# HF_TUNER.net
KiCad netlist of a schematic drawn in Altium Designer
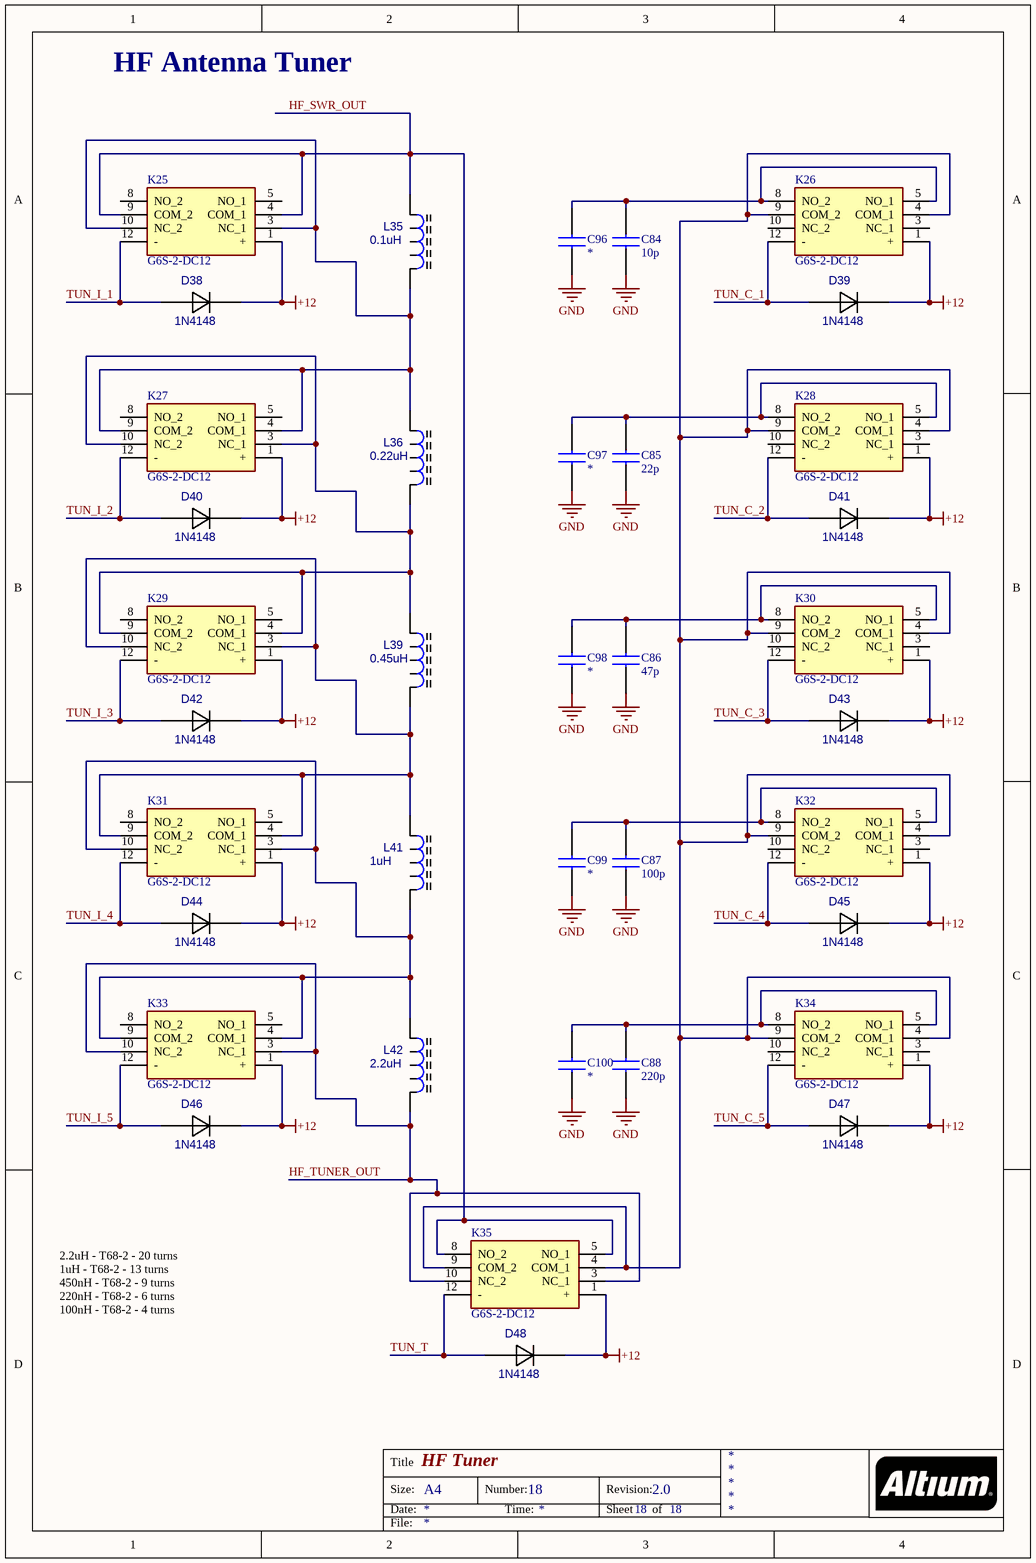
[diagram p0: HF_TUNER.SchDoc]

(export (version "E")
  (design (tool "Eeschema 10.0.6"))
  (components
    (comp (ref "C84")
      (value "10p")
      (footprint "SamacSys:B32620A0682J000")
      (description "Capacitor")
      (fields
        (field (name "MANUFACTURER_PART_NUMBER") "B32620A0682J000")
        (field (name "MOUSER PART NUMBER") "871-B32620A682J")
      )
      (libsource (lib "*") (part "B32620A0682J000"))
    )
    (comp (ref "C85")
      (value "22p")
      (footprint "SamacSys:B32620A0682J000")
      (description "Capacitor")
      (fields
        (field (name "MANUFACTURER_PART_NUMBER") "B32620A0682J000")
        (field (name "MOUSER PART NUMBER") "871-B32620A682J")
      )
      (libsource (lib "*") (part "B32620A0682J000"))
    )
    (comp (ref "C86")
      (value "47p")
      (footprint "SamacSys:B32620A0682J000")
      (description "Capacitor")
      (fields
        (field (name "MANUFACTURER_PART_NUMBER") "B32620A0682J000")
        (field (name "MOUSER PART NUMBER") "871-B32620A682J")
      )
      (libsource (lib "*") (part "B32620A0682J000"))
    )
    (comp (ref "C87")
      (value "100p")
      (footprint "SamacSys:B32620A0682J000")
      (description "Capacitor")
      (fields
        (field (name "MANUFACTURER_PART_NUMBER") "B32620A0682J000")
        (field (name "MOUSER PART NUMBER") "871-B32620A682J")
      )
      (libsource (lib "*") (part "B32620A0682J000"))
    )
    (comp (ref "C88")
      (value "220p")
      (footprint "SamacSys:B32620A0682J000")
      (description "Capacitor")
      (fields
        (field (name "MANUFACTURER_PART_NUMBER") "B32620A0682J000")
        (field (name "MOUSER PART NUMBER") "871-B32620A682J")
      )
      (libsource (lib "*") (part "B32620A0682J000"))
    )
    (comp (ref "C96")
      (value "*")
      (footprint "CAP_1206")
      (description "Capacitor NP0 HiVolt")
      (fields
        (field (name "MANUFACTURER_PART_NUMBER") "B32620A0682J000")
        (field (name "MOUSER PART NUMBER") "871-B32620A682J")
      )
      (libsource (lib "*") (part "B32620A0682J000"))
    )
    (comp (ref "C97")
      (value "*")
      (footprint "CAP_1206")
      (description "Capacitor NP0 HiVolt")
      (fields
        (field (name "MANUFACTURER_PART_NUMBER") "B32620A0682J000")
        (field (name "MOUSER PART NUMBER") "871-B32620A682J")
      )
      (libsource (lib "*") (part "B32620A0682J000"))
    )
    (comp (ref "C98")
      (value "*")
      (footprint "CAP_1206")
      (description "Capacitor NP0 HiVolt")
      (fields
        (field (name "MANUFACTURER_PART_NUMBER") "B32620A0682J000")
        (field (name "MOUSER PART NUMBER") "871-B32620A682J")
      )
      (libsource (lib "*") (part "B32620A0682J000"))
    )
    (comp (ref "C99")
      (value "*")
      (footprint "CAP_1206")
      (description "Capacitor NP0 HiVolt")
      (fields
        (field (name "MANUFACTURER_PART_NUMBER") "B32620A0682J000")
        (field (name "MOUSER PART NUMBER") "871-B32620A682J")
      )
      (libsource (lib "*") (part "B32620A0682J000"))
    )
    (comp (ref "C100")
      (value "*")
      (footprint "CAP_1206")
      (description "Capacitor NP0 HiVolt")
      (fields
        (field (name "MANUFACTURER_PART_NUMBER") "B32620A0682J000")
        (field (name "MOUSER PART NUMBER") "871-B32620A682J")
      )
      (libsource (lib "*") (part "B32620A0682J000"))
    )
    (comp (ref "D38") (value "1N4148") (footprint "SS14") (libsource (lib "RF-UNIT-BIG") (part "1N4148")))
    (comp (ref "D39") (value "1N4148") (footprint "SS14") (libsource (lib "RF-UNIT-BIG") (part "1N4148")))
    (comp (ref "D40") (value "1N4148") (footprint "SS14") (libsource (lib "RF-UNIT-BIG") (part "1N4148")))
    (comp (ref "D41") (value "1N4148") (footprint "SS14") (libsource (lib "RF-UNIT-BIG") (part "1N4148")))
    (comp (ref "D42") (value "1N4148") (footprint "SS14") (libsource (lib "RF-UNIT-BIG") (part "1N4148")))
    (comp (ref "D43") (value "1N4148") (footprint "SS14") (libsource (lib "RF-UNIT-BIG") (part "1N4148")))
    (comp (ref "D44") (value "1N4148") (footprint "SS14") (libsource (lib "RF-UNIT-BIG") (part "1N4148")))
    (comp (ref "D45") (value "1N4148") (footprint "SS14") (libsource (lib "RF-UNIT-BIG") (part "1N4148")))
    (comp (ref "D46") (value "1N4148") (footprint "SS14") (libsource (lib "RF-UNIT-BIG") (part "1N4148")))
    (comp (ref "D47") (value "1N4148") (footprint "SS14") (libsource (lib "RF-UNIT-BIG") (part "1N4148")))
    (comp (ref "D48") (value "1N4148") (footprint "SS14") (libsource (lib "RF-UNIT-BIG") (part "1N4148")))
    (comp (ref "K25")
      (value "G6S-2-DC12")
      (footprint "SamacSys:G6S2DC12")
      (description "Relay or Contactor")
      (fields (field (name "MOUSER PART NUMBER") "653-G6S-2-DC12A"))
      (libsource (lib "*") (part "G6S-2-DC12"))
    )
    (comp (ref "K26")
      (value "G6S-2-DC12")
      (footprint "SamacSys:G6S2DC12")
      (description "Relay or Contactor")
      (fields (field (name "MOUSER PART NUMBER") "653-G6S-2-DC12A"))
      (libsource (lib "*") (part "G6S-2-DC12"))
    )
    (comp (ref "K27")
      (value "G6S-2-DC12")
      (footprint "SamacSys:G6S2DC12")
      (description "Relay or Contactor")
      (fields (field (name "MOUSER PART NUMBER") "653-G6S-2-DC12A"))
      (libsource (lib "*") (part "G6S-2-DC12"))
    )
    (comp (ref "K28")
      (value "G6S-2-DC12")
      (footprint "SamacSys:G6S2DC12")
      (description "Relay or Contactor")
      (fields (field (name "MOUSER PART NUMBER") "653-G6S-2-DC12A"))
      (libsource (lib "*") (part "G6S-2-DC12"))
    )
    (comp (ref "K29")
      (value "G6S-2-DC12")
      (footprint "SamacSys:G6S2DC12")
      (description "Relay or Contactor")
      (fields (field (name "MOUSER PART NUMBER") "653-G6S-2-DC12A"))
      (libsource (lib "*") (part "G6S-2-DC12"))
    )
    (comp (ref "K30")
      (value "G6S-2-DC12")
      (footprint "SamacSys:G6S2DC12")
      (description "Relay or Contactor")
      (fields (field (name "MOUSER PART NUMBER") "653-G6S-2-DC12A"))
      (libsource (lib "*") (part "G6S-2-DC12"))
    )
    (comp (ref "K31")
      (value "G6S-2-DC12")
      (footprint "SamacSys:G6S2DC12")
      (description "Relay or Contactor")
      (fields (field (name "MOUSER PART NUMBER") "653-G6S-2-DC12A"))
      (libsource (lib "*") (part "G6S-2-DC12"))
    )
    (comp (ref "K32")
      (value "G6S-2-DC12")
      (footprint "SamacSys:G6S2DC12")
      (description "Relay or Contactor")
      (fields (field (name "MOUSER PART NUMBER") "653-G6S-2-DC12A"))
      (libsource (lib "*") (part "G6S-2-DC12"))
    )
    (comp (ref "K33")
      (value "G6S-2-DC12")
      (footprint "SamacSys:G6S2DC12")
      (description "Relay or Contactor")
      (fields (field (name "MOUSER PART NUMBER") "653-G6S-2-DC12A"))
      (libsource (lib "*") (part "G6S-2-DC12"))
    )
    (comp (ref "K34")
      (value "G6S-2-DC12")
      (footprint "SamacSys:G6S2DC12")
      (description "Relay or Contactor")
      (fields (field (name "MOUSER PART NUMBER") "653-G6S-2-DC12A"))
      (libsource (lib "*") (part "G6S-2-DC12"))
    )
    (comp (ref "K35")
      (value "G6S-2-DC12")
      (footprint "SamacSys:G6S2DC12")
      (description "Relay or Contactor")
      (fields (field (name "MOUSER PART NUMBER") "653-G6S-2-DC12A"))
      (libsource (lib "*") (part "G6S-2-DC12"))
    )
    (comp (ref "L35")
      (value "0.1uH")
      (footprint "IND_FERRITE_CORE_1")
      (description "Inductor")
      (libsource (lib "*") (part "IND_FERRITE_CORE"))
    )
    (comp (ref "L36")
      (value "0.22uH")
      (footprint "IND_FERRITE_CORE_1")
      (description "Inductor")
      (libsource (lib "*") (part "IND_FERRITE_CORE"))
    )
    (comp (ref "L39")
      (value "0.45uH")
      (footprint "IND_FERRITE_CORE_1")
      (description "Inductor")
      (libsource (lib "*") (part "IND_FERRITE_CORE"))
    )
    (comp (ref "L41")
      (value "1uH")
      (footprint "IND_FERRITE_CORE_1")
      (description "Inductor")
      (libsource (lib "*") (part "IND_FERRITE_CORE"))
    )
    (comp (ref "L42")
      (value "2.2uH")
      (footprint "IND_FERRITE_CORE_1")
      (description "Inductor")
      (libsource (lib "*") (part "IND_FERRITE_CORE"))
    )
  )
  (nets
    (net (code "1") (name "+12") (class "Default")
      (node (ref "D38") (pin "1") (pinfunction "K_1") (pintype "passive"))
      (node (ref "D39") (pin "1") (pinfunction "K_1") (pintype "passive"))
      (node (ref "D40") (pin "1") (pinfunction "K_1") (pintype "passive"))
      (node (ref "D41") (pin "1") (pinfunction "K_1") (pintype "passive"))
      (node (ref "D42") (pin "1") (pinfunction "K_1") (pintype "passive"))
      (node (ref "D43") (pin "1") (pinfunction "K_1") (pintype "passive"))
      (node (ref "D44") (pin "1") (pinfunction "K_1") (pintype "passive"))
      (node (ref "D45") (pin "1") (pinfunction "K_1") (pintype "passive"))
      (node (ref "D46") (pin "1") (pinfunction "K_1") (pintype "passive"))
      (node (ref "D47") (pin "1") (pinfunction "K_1") (pintype "passive"))
      (node (ref "D48") (pin "1") (pinfunction "K_1") (pintype "passive"))
      (node (ref "K25") (pin "1") (pinfunction "+_1") (pintype "passive"))
      (node (ref "K26") (pin "1") (pinfunction "+_1") (pintype "passive"))
      (node (ref "K27") (pin "1") (pinfunction "+_1") (pintype "passive"))
      (node (ref "K28") (pin "1") (pinfunction "+_1") (pintype "passive"))
      (node (ref "K29") (pin "1") (pinfunction "+_1") (pintype "passive"))
      (node (ref "K30") (pin "1") (pinfunction "+_1") (pintype "passive"))
      (node (ref "K31") (pin "1") (pinfunction "+_1") (pintype "passive"))
      (node (ref "K32") (pin "1") (pinfunction "+_1") (pintype "passive"))
      (node (ref "K33") (pin "1") (pinfunction "+_1") (pintype "passive"))
      (node (ref "K34") (pin "1") (pinfunction "+_1") (pintype "passive"))
      (node (ref "K35") (pin "1") (pinfunction "+_1") (pintype "passive"))
    )
    (net (code "2") (name "/HF_SWR_OUT") (class "Default")
      (node (ref "K25") (pin "4") (pinfunction "COM_1_4") (pintype "passive"))
      (node (ref "K25") (pin "9") (pinfunction "COM_2_9") (pintype "passive"))
      (node (ref "K35") (pin "5") (pinfunction "NO_1_5") (pintype "passive"))
      (node (ref "K35") (pin "8") (pinfunction "NO_2_8") (pintype "passive"))
      (node (ref "L35") (pin "1") (pinfunction "A_1") (pintype "passive"))
    )
    (net (code "3") (name "/HF_TUNER_OUT") (class "Default")
      (node (ref "K33") (pin "10") (pinfunction "NC_2_10") (pintype "passive"))
      (node (ref "K33") (pin "3") (pinfunction "NC_1_3") (pintype "passive"))
      (node (ref "K35") (pin "10") (pinfunction "NC_2_10") (pintype "passive"))
      (node (ref "K35") (pin "3") (pinfunction "NC_1_3") (pintype "passive"))
      (node (ref "L42") (pin "2") (pinfunction "B_2") (pintype "passive"))
    )
    (net (code "4") (name "/TUN_I_1") (class "Default")
      (node (ref "D38") (pin "2") (pinfunction "A_2") (pintype "passive"))
      (node (ref "K25") (pin "12") (pinfunction "-_12") (pintype "passive"))
    )
    (net (code "5") (name "/TUN_I_2") (class "Default")
      (node (ref "D40") (pin "2") (pinfunction "A_2") (pintype "passive"))
      (node (ref "K27") (pin "12") (pinfunction "-_12") (pintype "passive"))
    )
    (net (code "6") (name "/TUN_I_3") (class "Default")
      (node (ref "D42") (pin "2") (pinfunction "A_2") (pintype "passive"))
      (node (ref "K29") (pin "12") (pinfunction "-_12") (pintype "passive"))
    )
    (net (code "7") (name "/TUN_I_4") (class "Default")
      (node (ref "D44") (pin "2") (pinfunction "A_2") (pintype "passive"))
      (node (ref "K31") (pin "12") (pinfunction "-_12") (pintype "passive"))
    )
    (net (code "8") (name "/TUN_I_5") (class "Default")
      (node (ref "D46") (pin "2") (pinfunction "A_2") (pintype "passive"))
      (node (ref "K33") (pin "12") (pinfunction "-_12") (pintype "passive"))
    )
    (net (code "9") (name "/TUN_T") (class "Default")
      (node (ref "D48") (pin "2") (pinfunction "A_2") (pintype "passive"))
      (node (ref "K35") (pin "12") (pinfunction "-_12") (pintype "passive"))
    )
    (net (code "10") (name "/TUN_С_1") (class "Default")
      (node (ref "D39") (pin "2") (pinfunction "A_2") (pintype "passive"))
      (node (ref "K26") (pin "12") (pinfunction "-_12") (pintype "passive"))
    )
    (net (code "11") (name "/TUN_С_2") (class "Default")
      (node (ref "D41") (pin "2") (pinfunction "A_2") (pintype "passive"))
      (node (ref "K28") (pin "12") (pinfunction "-_12") (pintype "passive"))
    )
    (net (code "12") (name "/TUN_С_3") (class "Default")
      (node (ref "D43") (pin "2") (pinfunction "A_2") (pintype "passive"))
      (node (ref "K30") (pin "12") (pinfunction "-_12") (pintype "passive"))
    )
    (net (code "13") (name "/TUN_С_4") (class "Default")
      (node (ref "D45") (pin "2") (pinfunction "A_2") (pintype "passive"))
      (node (ref "K32") (pin "12") (pinfunction "-_12") (pintype "passive"))
    )
    (net (code "14") (name "/TUN_С_5") (class "Default")
      (node (ref "D47") (pin "2") (pinfunction "A_2") (pintype "passive"))
      (node (ref "K34") (pin "12") (pinfunction "-_12") (pintype "passive"))
    )
    (net (code "15") (name "GND") (class "Default")
      (node (ref "C100") (pin "1") (pinfunction "1_1") (pintype "passive"))
      (node (ref "C84") (pin "1") (pinfunction "1_1") (pintype "passive"))
      (node (ref "C85") (pin "1") (pinfunction "1_1") (pintype "passive"))
      (node (ref "C86") (pin "1") (pinfunction "1_1") (pintype "passive"))
      (node (ref "C87") (pin "1") (pinfunction "1_1") (pintype "passive"))
      (node (ref "C88") (pin "1") (pinfunction "1_1") (pintype "passive"))
      (node (ref "C96") (pin "1") (pinfunction "1_1") (pintype "passive"))
      (node (ref "C97") (pin "1") (pinfunction "1_1") (pintype "passive"))
      (node (ref "C98") (pin "1") (pinfunction "1_1") (pintype "passive"))
      (node (ref "C99") (pin "1") (pinfunction "1_1") (pintype "passive"))
    )
    (net (code "16") (name "Net-(K25-NC_1)") (class "Default")
      (node (ref "K25") (pin "10") (pinfunction "NC_2_10") (pintype "passive"))
      (node (ref "K25") (pin "3") (pinfunction "NC_1_3") (pintype "passive"))
      (node (ref "K27") (pin "4") (pinfunction "COM_1_4") (pintype "passive"))
      (node (ref "K27") (pin "9") (pinfunction "COM_2_9") (pintype "passive"))
      (node (ref "L35") (pin "2") (pinfunction "B_2") (pintype "passive"))
      (node (ref "L36") (pin "1") (pinfunction "A_1") (pintype "passive"))
    )
    (net (code "17") (name "Net-(K26-COM_1)") (class "Default")
      (node (ref "K26") (pin "4") (pinfunction "COM_1_4") (pintype "passive"))
      (node (ref "K26") (pin "9") (pinfunction "COM_2_9") (pintype "passive"))
      (node (ref "K28") (pin "4") (pinfunction "COM_1_4") (pintype "passive"))
      (node (ref "K28") (pin "9") (pinfunction "COM_2_9") (pintype "passive"))
      (node (ref "K30") (pin "4") (pinfunction "COM_1_4") (pintype "passive"))
      (node (ref "K30") (pin "9") (pinfunction "COM_2_9") (pintype "passive"))
      (node (ref "K32") (pin "4") (pinfunction "COM_1_4") (pintype "passive"))
      (node (ref "K32") (pin "9") (pinfunction "COM_2_9") (pintype "passive"))
      (node (ref "K34") (pin "4") (pinfunction "COM_1_4") (pintype "passive"))
      (node (ref "K34") (pin "9") (pinfunction "COM_2_9") (pintype "passive"))
      (node (ref "K35") (pin "4") (pinfunction "COM_1_4") (pintype "passive"))
      (node (ref "K35") (pin "9") (pinfunction "COM_2_9") (pintype "passive"))
    )
    (net (code "18") (name "Net-(K26-NO_1)") (class "Default")
      (node (ref "C84") (pin "2") (pinfunction "2_2") (pintype "passive"))
      (node (ref "C96") (pin "2") (pinfunction "2_2") (pintype "passive"))
      (node (ref "K26") (pin "5") (pinfunction "NO_1_5") (pintype "passive"))
      (node (ref "K26") (pin "8") (pinfunction "NO_2_8") (pintype "passive"))
    )
    (net (code "19") (name "Net-(K27-NC_1)") (class "Default")
      (node (ref "K27") (pin "10") (pinfunction "NC_2_10") (pintype "passive"))
      (node (ref "K27") (pin "3") (pinfunction "NC_1_3") (pintype "passive"))
      (node (ref "K29") (pin "4") (pinfunction "COM_1_4") (pintype "passive"))
      (node (ref "K29") (pin "9") (pinfunction "COM_2_9") (pintype "passive"))
      (node (ref "L36") (pin "2") (pinfunction "B_2") (pintype "passive"))
      (node (ref "L39") (pin "1") (pinfunction "A_1") (pintype "passive"))
    )
    (net (code "20") (name "Net-(K28-NO_1)") (class "Default")
      (node (ref "C85") (pin "2") (pinfunction "2_2") (pintype "passive"))
      (node (ref "C97") (pin "2") (pinfunction "2_2") (pintype "passive"))
      (node (ref "K28") (pin "5") (pinfunction "NO_1_5") (pintype "passive"))
      (node (ref "K28") (pin "8") (pinfunction "NO_2_8") (pintype "passive"))
    )
    (net (code "21") (name "Net-(K29-NC_1)") (class "Default")
      (node (ref "K29") (pin "10") (pinfunction "NC_2_10") (pintype "passive"))
      (node (ref "K29") (pin "3") (pinfunction "NC_1_3") (pintype "passive"))
      (node (ref "K31") (pin "4") (pinfunction "COM_1_4") (pintype "passive"))
      (node (ref "K31") (pin "9") (pinfunction "COM_2_9") (pintype "passive"))
      (node (ref "L39") (pin "2") (pinfunction "B_2") (pintype "passive"))
      (node (ref "L41") (pin "1") (pinfunction "A_1") (pintype "passive"))
    )
    (net (code "22") (name "Net-(K30-NO_1)") (class "Default")
      (node (ref "C86") (pin "2") (pinfunction "2_2") (pintype "passive"))
      (node (ref "C98") (pin "2") (pinfunction "2_2") (pintype "passive"))
      (node (ref "K30") (pin "5") (pinfunction "NO_1_5") (pintype "passive"))
      (node (ref "K30") (pin "8") (pinfunction "NO_2_8") (pintype "passive"))
    )
    (net (code "23") (name "Net-(K31-NC_1)") (class "Default")
      (node (ref "K31") (pin "10") (pinfunction "NC_2_10") (pintype "passive"))
      (node (ref "K31") (pin "3") (pinfunction "NC_1_3") (pintype "passive"))
      (node (ref "K33") (pin "4") (pinfunction "COM_1_4") (pintype "passive"))
      (node (ref "K33") (pin "9") (pinfunction "COM_2_9") (pintype "passive"))
      (node (ref "L41") (pin "2") (pinfunction "B_2") (pintype "passive"))
      (node (ref "L42") (pin "1") (pinfunction "A_1") (pintype "passive"))
    )
    (net (code "24") (name "Net-(K32-NO_1)") (class "Default")
      (node (ref "C87") (pin "2") (pinfunction "2_2") (pintype "passive"))
      (node (ref "C99") (pin "2") (pinfunction "2_2") (pintype "passive"))
      (node (ref "K32") (pin "5") (pinfunction "NO_1_5") (pintype "passive"))
      (node (ref "K32") (pin "8") (pinfunction "NO_2_8") (pintype "passive"))
    )
    (net (code "25") (name "Net-(K34-NO_1)") (class "Default")
      (node (ref "C100") (pin "2") (pinfunction "2_2") (pintype "passive"))
      (node (ref "C88") (pin "2") (pinfunction "2_2") (pintype "passive"))
      (node (ref "K34") (pin "5") (pinfunction "NO_1_5") (pintype "passive"))
      (node (ref "K34") (pin "8") (pinfunction "NO_2_8") (pintype "passive"))
    )
    (net (code "26") (name "unconnected-(K25-NO_1-Pad5)") (class "Default")
      (node (ref "K25") (pin "5") (pinfunction "NO_1_5") (pintype "passive"))
    )
    (net (code "27") (name "unconnected-(K25-NO_2-Pad8)") (class "Default")
      (node (ref "K25") (pin "8") (pinfunction "NO_2_8") (pintype "passive"))
    )
    (net (code "28") (name "unconnected-(K26-NC_1-Pad3)") (class "Default")
      (node (ref "K26") (pin "3") (pinfunction "NC_1_3") (pintype "passive"))
    )
    (net (code "29") (name "unconnected-(K26-NC_2-Pad10)") (class "Default")
      (node (ref "K26") (pin "10") (pinfunction "NC_2_10") (pintype "passive"))
    )
    (net (code "30") (name "unconnected-(K27-NO_1-Pad5)") (class "Default")
      (node (ref "K27") (pin "5") (pinfunction "NO_1_5") (pintype "passive"))
    )
    (net (code "31") (name "unconnected-(K27-NO_2-Pad8)") (class "Default")
      (node (ref "K27") (pin "8") (pinfunction "NO_2_8") (pintype "passive"))
    )
    (net (code "32") (name "unconnected-(K28-NC_1-Pad3)") (class "Default")
      (node (ref "K28") (pin "3") (pinfunction "NC_1_3") (pintype "passive"))
    )
    (net (code "33") (name "unconnected-(K28-NC_2-Pad10)") (class "Default")
      (node (ref "K28") (pin "10") (pinfunction "NC_2_10") (pintype "passive"))
    )
    (net (code "34") (name "unconnected-(K29-NO_1-Pad5)") (class "Default")
      (node (ref "K29") (pin "5") (pinfunction "NO_1_5") (pintype "passive"))
    )
    (net (code "35") (name "unconnected-(K29-NO_2-Pad8)") (class "Default")
      (node (ref "K29") (pin "8") (pinfunction "NO_2_8") (pintype "passive"))
    )
    (net (code "36") (name "unconnected-(K30-NC_1-Pad3)") (class "Default")
      (node (ref "K30") (pin "3") (pinfunction "NC_1_3") (pintype "passive"))
    )
    (net (code "37") (name "unconnected-(K30-NC_2-Pad10)") (class "Default")
      (node (ref "K30") (pin "10") (pinfunction "NC_2_10") (pintype "passive"))
    )
    (net (code "38") (name "unconnected-(K31-NO_1-Pad5)") (class "Default")
      (node (ref "K31") (pin "5") (pinfunction "NO_1_5") (pintype "passive"))
    )
    (net (code "39") (name "unconnected-(K31-NO_2-Pad8)") (class "Default")
      (node (ref "K31") (pin "8") (pinfunction "NO_2_8") (pintype "passive"))
    )
    (net (code "40") (name "unconnected-(K32-NC_1-Pad3)") (class "Default")
      (node (ref "K32") (pin "3") (pinfunction "NC_1_3") (pintype "passive"))
    )
    (net (code "41") (name "unconnected-(K32-NC_2-Pad10)") (class "Default")
      (node (ref "K32") (pin "10") (pinfunction "NC_2_10") (pintype "passive"))
    )
    (net (code "42") (name "unconnected-(K33-NO_1-Pad5)") (class "Default")
      (node (ref "K33") (pin "5") (pinfunction "NO_1_5") (pintype "passive"))
    )
    (net (code "43") (name "unconnected-(K33-NO_2-Pad8)") (class "Default")
      (node (ref "K33") (pin "8") (pinfunction "NO_2_8") (pintype "passive"))
    )
    (net (code "44") (name "unconnected-(K34-NC_1-Pad3)") (class "Default")
      (node (ref "K34") (pin "3") (pinfunction "NC_1_3") (pintype "passive"))
    )
    (net (code "45") (name "unconnected-(K34-NC_2-Pad10)") (class "Default")
      (node (ref "K34") (pin "10") (pinfunction "NC_2_10") (pintype "passive"))
    )
  )
)
